# Neopixel_Driver.net
KiCad netlist of a schematic drawn in Altium Designer
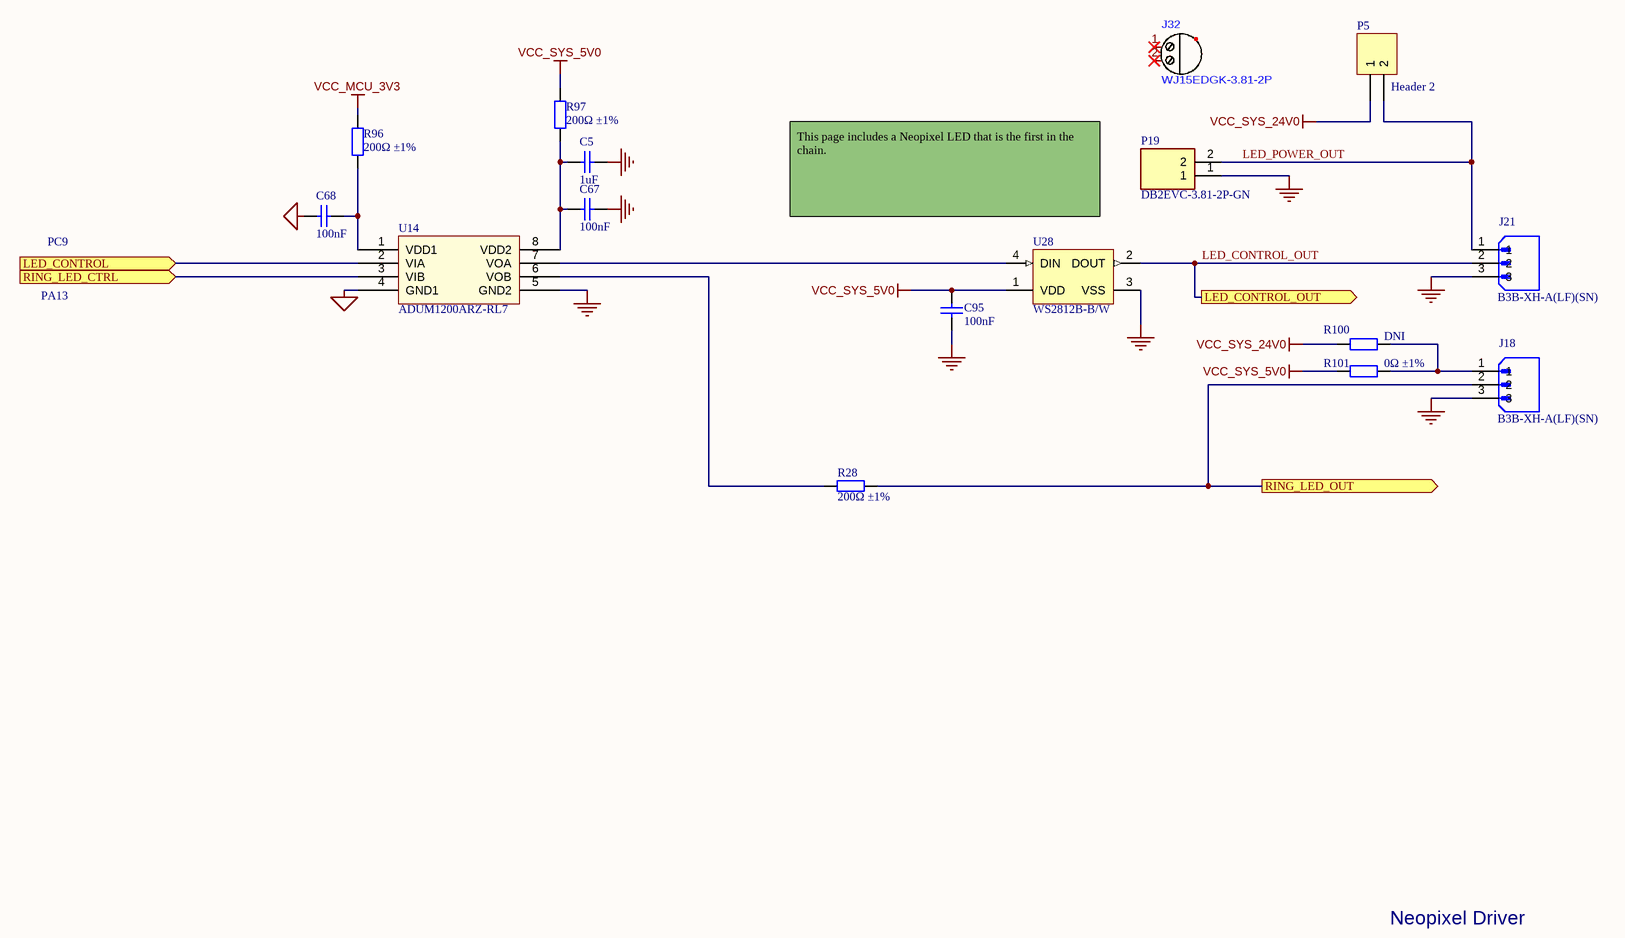
[diagram p0: Neopixel_Driver.SchDoc]

(export (version "E")
  (design (tool "Eeschema 10.0.6"))
  (components
    (comp (ref "C5")
      (value "1uF")
      (footprint "0603_C")
      (description "Chip capacitors")
      (fields (field (name "MANUFACTURER") "Samsung Electro-Mechanics") (field (name "TOLERANCE") "10%"))
      (libsource (lib "Sienci_Labs") (part "0603 1uF (105) 10% 50V"))
    )
    (comp (ref "C67")
      (value "100nF")
      (footprint "0603_C")
      (description "50V 100nF X7R ±10% 0603 Multilayer Ceramic Capacitors MLCC - SMD/SMT ROHS")
      (fields (field (name "MANUFACTURER") "YAGEO") (field (name "TOLERANCE") "10%"))
      (libsource (lib "Sienci_Labs") (part "0603 100nF (104) 10% 50V"))
    )
    (comp (ref "C68")
      (value "100nF")
      (footprint "0603_C")
      (description "50V 100nF X7R ±10% 0603 Multilayer Ceramic Capacitors MLCC - SMD/SMT ROHS")
      (fields (field (name "MANUFACTURER") "YAGEO") (field (name "TOLERANCE") "10%"))
      (libsource (lib "Sienci_Labs") (part "0603 100nF (104) 10% 50V"))
    )
    (comp (ref "C95")
      (value "100nF")
      (footprint "0603_C")
      (description "50V 100nF X7R ±10% 0603 Multilayer Ceramic Capacitors MLCC - SMD/SMT ROHS")
      (fields
        (field (name "MANUFACTURER") "YAGEO")
        (field (name "MANUFACTURER PART NUMBER") "CC0603KRX7R9BB104")
      )
      (libsource (lib "Sienci_Labs") (part "0603 100nF (104) 10% 50V"))
    )
    (comp (ref "J18")
      (value "B3B-XH-A(LF)(SN)")
      (footprint "JST_B3B-XH-A(LF)(SN)")
      (description "Connector Header Through Hole 3 position 0.098\" (2.50mm)")
      (fields (field (name "MANUFACTURER") "JST Sales America"))
      (libsource (lib "Sienci_Labs") (part "B3B-XH-A(LF)(SN)"))
    )
    (comp (ref "J21")
      (value "B3B-XH-A(LF)(SN)")
      (footprint "JST_B3B-XH-A(LF)(SN)")
      (description "Connector Header Through Hole 3 position 0.098\" (2.50mm)")
      (fields (field (name "MANUFACTURER") "JST Sales America"))
      (libsource (lib "Sienci_Labs") (part "B3B-XH-A(LF)(SN)"))
    )
    (comp (ref "J32")
      (value "WJ15EDGK-3.81-2P")
      (description "2 1 3.81mm Green Plug P=3.81mm Pluggable System Terminal Block ROHS")
      (fields (field (name "MANUFACTURER") "Ningbo"))
      (libsource (lib "Sienci_Labs") (part "WJ15EDGK-3.81-2P"))
    )
    (comp (ref "P5")
      (value "Header 2")
      (footprint "HDR1X2")
      (description "Straight Square Pins 2 2.54mm Black Brass 1x2P Plugin,P=2.54mm Pin Headers ROHS")
      (fields
        (field (name "MANUFACTURER") "MOLEX")
        (field (name "MANUFACTURER PART NUMBER") "22284020")
        (field (name "PUBLISHER") "Altium Limited")
      )
      (libsource (lib "Sienci_Labs") (part "Header 2"))
    )
    (comp (ref "P19")
      (value "DB2EVC-3.81-2P-GN")
      (footprint "CONN-TH_5P-P3.81_DB2EVC-3.81-2p")
      (description "3.81mm Green Board Edge/Receptacle-Close Push-Pull,P=3.81mm Pluggable System Terminal Block ROHS")
      (fields (field (name "MANUFACTURER") "DIBO"))
      (libsource (lib "Sienci_Labs") (part "DB2EVC-3.81-2P-GN"))
    )
    (comp (ref "R28")
      (value "200Ω ±1%")
      (footprint "0402_R")
      (description "Chip resistor")
      (fields
        (field (name "MANUFACTURER") "Uniroyal Elec")
        (field (name "MANUFACTURER PART NUMBER") "0402WGF2000TCE")
      )
      (libsource (lib "") (part "0402 200R (2000) 1%_1"))
    )
    (comp (ref "R96")
      (value "200Ω ±1%")
      (footprint "0402_R")
      (description "Chip resistor")
      (fields
        (field (name "MANUFACTURER") "Uniroyal Elec")
        (field (name "MANUFACTURER PART NUMBER") "0402WGF2000TCE")
      )
      (libsource (lib "RES") (part "0402 200R (2000) 1%"))
    )
    (comp (ref "R97")
      (value "200Ω ±1%")
      (footprint "0402_R")
      (description "Chip resistor")
      (fields
        (field (name "MANUFACTURER") "Uniroyal Elec")
        (field (name "MANUFACTURER PART NUMBER") "0402WGF2000TCE")
      )
      (libsource (lib "RES") (part "0402 200R (2000) 1%"))
    )
    (comp (ref "R100")
      (value "DNI")
      (footprint "0603_R")
      (description "Chip resistor")
      (fields
        (field (name "MANUFACTURER") "Uniroyal Elec")
        (field (name "MANUFACTURER PART NUMBER") "0603WAF0000T5E")
      )
      (libsource (lib "Sienci_Labs") (part "0603 0R (0R0) 1%"))
    )
    (comp (ref "R101")
      (value "0Ω ±1%")
      (footprint "0603_R")
      (description "Chip resistor")
      (fields
        (field (name "MANUFACTURER") "Uniroyal Elec")
        (field (name "MANUFACTURER PART NUMBER") "0603WAF0000T5E")
      )
      (libsource (lib "Sienci_Labs") (part "0603 0R (0R0) 1%"))
    )
    (comp (ref "U14")
      (value "ADUM1200ARZ-RL7")
      (footprint "SOIC-8_150mil")
      (description "Dual Channel Isolator")
      (fields (field (name "MANUFACTURER") "Analog Devices"))
      (libsource (lib "Sienci_Labs") (part "ADUM1200ARZ-RL7"))
    )
    (comp (ref "U28")
      (value "WS2812B-B/W")
      (footprint "ADA-RGB-1655_V")
      (fields (field (name "MANUFACTURER") "Worldsemi"))
      (libsource (lib "Sienci_Labs") (part "WS2812B-B/W"))
    )
  )
  (nets
    (net (code "1") (name "/LED_CONTROL") (class "Default")
      (node (ref "U14") (pin "2") (pinfunction "VIA_2") (pintype "passive"))
    )
    (net (code "2") (name "/LED_CONTROL_OUT") (class "Default")
      (node (ref "J21") (pin "2") (pinfunction "2_2") (pintype "passive"))
      (node (ref "U28") (pin "2") (pinfunction "DOUT_2") (pintype "output"))
    )
    (net (code "3") (name "/LED_POWER_OUT") (class "Default")
      (node (ref "J21") (pin "1") (pinfunction "1_1") (pintype "passive"))
      (node (ref "P19") (pin "2") (pinfunction "2_2") (pintype "passive"))
      (node (ref "P5") (pin "2") (pinfunction "2_2") (pintype "passive"))
    )
    (net (code "4") (name "/RING_LED_CTRL") (class "Default")
      (node (ref "U14") (pin "3") (pinfunction "VIB_3") (pintype "passive"))
    )
    (net (code "5") (name "/RING_LED_OUT") (class "Default")
      (node (ref "J18") (pin "2") (pinfunction "2_2") (pintype "passive"))
      (node (ref "R28") (pin "1") (pinfunction "1_1") (pintype "passive"))
    )
    (net (code "6") (name "GND") (class "Default")
      (node (ref "C5") (pin "1") (pinfunction "1_1") (pintype "passive"))
      (node (ref "C67") (pin "1") (pinfunction "1_1") (pintype "passive"))
      (node (ref "C95") (pin "1") (pinfunction "1_1") (pintype "passive"))
      (node (ref "J18") (pin "3") (pinfunction "3_3") (pintype "passive"))
      (node (ref "J21") (pin "3") (pinfunction "3_3") (pintype "passive"))
      (node (ref "P19") (pin "1") (pinfunction "1_1") (pintype "passive"))
      (node (ref "U14") (pin "5") (pinfunction "GND2_5") (pintype "passive"))
      (node (ref "U28") (pin "3") (pinfunction "VSS_3") (pintype "power_in"))
    )
    (net (code "7") (name "MCU_GND") (class "Default")
      (node (ref "C68") (pin "2") (pinfunction "2_2") (pintype "passive"))
      (node (ref "U14") (pin "4") (pinfunction "GND1_4") (pintype "passive"))
    )
    (net (code "8") (name "Net-(J18-Pad1)") (class "Default")
      (node (ref "J18") (pin "1") (pinfunction "1_1") (pintype "passive"))
      (node (ref "R100") (pin "1") (pinfunction "1_1") (pintype "passive"))
      (node (ref "R101") (pin "1") (pinfunction "1_1") (pintype "passive"))
    )
    (net (code "9") (name "Net-(U14-VDD1)") (class "Default")
      (node (ref "C68") (pin "1") (pinfunction "1_1") (pintype "passive"))
      (node (ref "R96") (pin "1") (pinfunction "1_1") (pintype "passive"))
      (node (ref "U14") (pin "1") (pinfunction "VDD1_1") (pintype "passive"))
    )
    (net (code "10") (name "Net-(U14-VDD2)") (class "Default")
      (node (ref "C5") (pin "2") (pinfunction "2_2") (pintype "passive"))
      (node (ref "C67") (pin "2") (pinfunction "2_2") (pintype "passive"))
      (node (ref "R97") (pin "1") (pinfunction "1_1") (pintype "passive"))
      (node (ref "U14") (pin "8") (pinfunction "VDD2_8") (pintype "passive"))
    )
    (net (code "11") (name "Net-(U14-VOA)") (class "Default")
      (node (ref "U14") (pin "7") (pinfunction "VOA_7") (pintype "passive"))
      (node (ref "U28") (pin "4") (pinfunction "DIN_4") (pintype "input"))
    )
    (net (code "12") (name "Net-(U14-VOB)") (class "Default")
      (node (ref "R28") (pin "2") (pinfunction "2_2") (pintype "passive"))
      (node (ref "U14") (pin "6") (pinfunction "VOB_6") (pintype "passive"))
    )
    (net (code "13") (name "VCC_MCU_3V3") (class "Default")
      (node (ref "R96") (pin "2") (pinfunction "2_2") (pintype "passive"))
    )
    (net (code "14") (name "VCC_SYS_5V0") (class "Default")
      (node (ref "C95") (pin "2") (pinfunction "2_2") (pintype "passive"))
      (node (ref "R101") (pin "2") (pinfunction "2_2") (pintype "passive"))
      (node (ref "R97") (pin "2") (pinfunction "2_2") (pintype "passive"))
      (node (ref "U28") (pin "1") (pinfunction "VDD_1") (pintype "power_in"))
    )
    (net (code "15") (name "VCC_SYS_24V0") (class "Default")
      (node (ref "P5") (pin "1") (pinfunction "1_1") (pintype "passive"))
      (node (ref "R100") (pin "2") (pinfunction "2_2") (pintype "passive"))
    )
    (net (code "16") (name "unconnected-(J32-Pad1)") (class "Default")
      (node (ref "J32") (pin "1") (pinfunction "1_1") (pintype "passive+no_connect"))
    )
    (net (code "17") (name "unconnected-(J32-Pad2)") (class "Default")
      (node (ref "J32") (pin "2") (pinfunction "2_2") (pintype "passive+no_connect"))
    )
  )
)
